# M119X.net
KiCad netlist of a schematic drawn in EAGLE
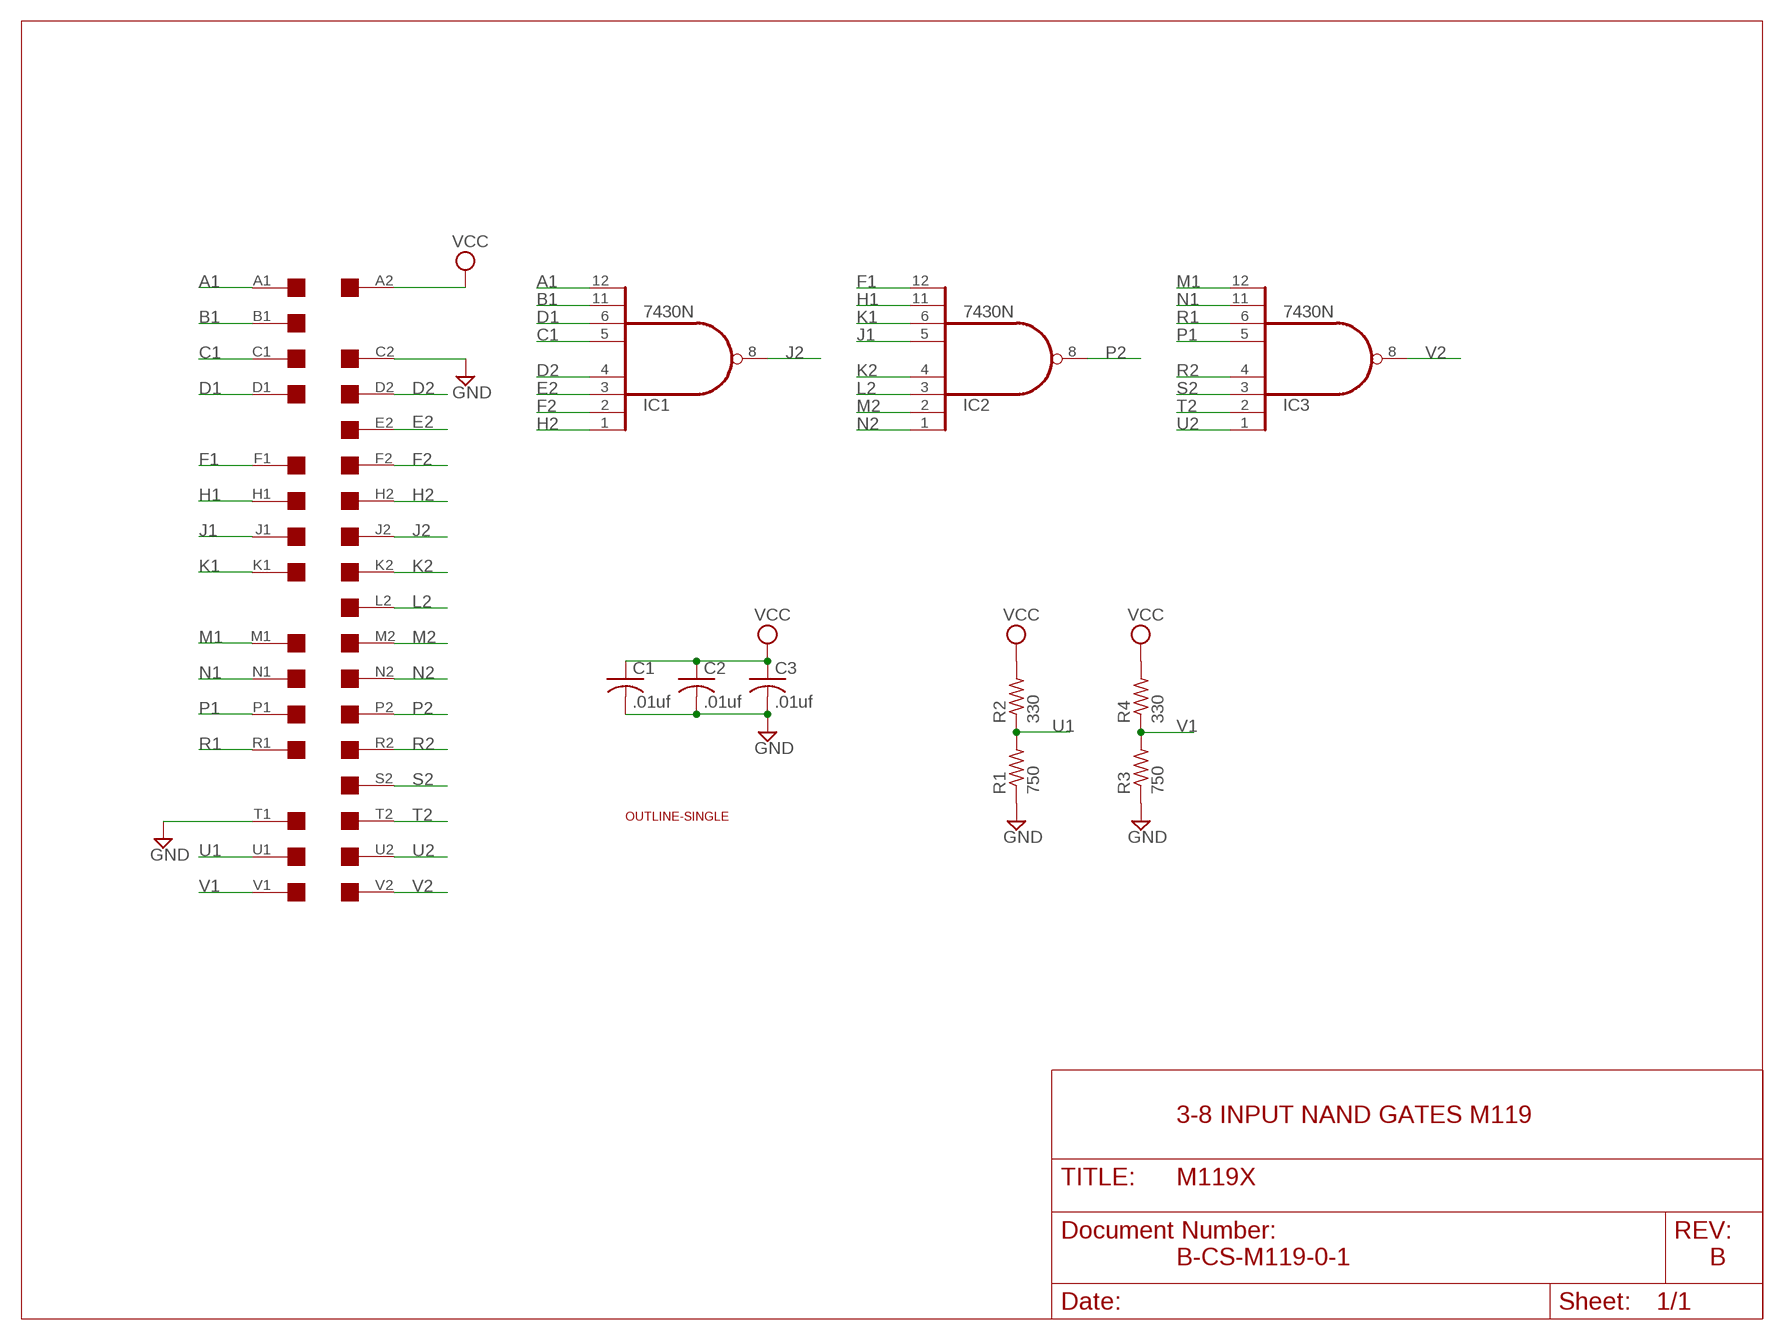
[diagram p0: schematic, sheet 1]

(export (version "E")
  (design (tool "Eeschema 10.0.6"))
  (components
    (comp (ref "C1")
      (value ".01uf")
      (footprint "eagle-import:C050-025X075")
      (libsource (lib "eagle-import") (part "C-US050-025X075"))
    )
    (comp (ref "C2")
      (value ".01uf")
      (footprint "eagle-import:C050-025X075")
      (libsource (lib "eagle-import") (part "C-US050-025X075"))
    )
    (comp (ref "C3")
      (value ".01uf")
      (footprint "eagle-import:C050-025X075")
      (libsource (lib "eagle-import") (part "C-US050-025X075"))
    )
    (comp (ref "IC1")
      (value "7430N")
      (footprint "eagle-import:DIL14")
      (libsource (lib "eagle-import") (part "7430N"))
    )
    (comp (ref "IC2")
      (value "7430N")
      (footprint "eagle-import:DIL14")
      (libsource (lib "eagle-import") (part "7430N"))
    )
    (comp (ref "IC3")
      (value "7430N")
      (footprint "eagle-import:DIL14")
      (libsource (lib "eagle-import") (part "7430N"))
    )
    (comp (ref "R1")
      (value "750")
      (footprint "eagle-import:0207_10")
      (libsource (lib "eagle-import") (part "R-US_0207/10"))
    )
    (comp (ref "R2")
      (value "330")
      (footprint "eagle-import:0207_10")
      (libsource (lib "eagle-import") (part "R-US_0207/10"))
    )
    (comp (ref "R3")
      (value "750")
      (footprint "eagle-import:0207_10")
      (libsource (lib "eagle-import") (part "R-US_0207/10"))
    )
    (comp (ref "R4")
      (value "330")
      (footprint "eagle-import:0207_10")
      (libsource (lib "eagle-import") (part "R-US_0207/10"))
    )
    (comp (ref "U$1")
      (value "OUTLINE-SINGLE")
      (footprint "eagle-import:SINGLE")
      (libsource (lib "eagle-import") (part "OUTLINE-SINGLE"))
    )
    (comp (ref "U$4")
      (value "SINGLE")
      (footprint "eagle-import:EDGE-CON2")
      (libsource (lib "eagle-import") (part "SINGLE"))
    )
  )
  (nets
    (net (code "1") (name "/A1") (class "Default")
      (node (ref "IC1") (pin "12") (pinfunction "I7_12") (pintype "input"))
      (node (ref "U$4") (pin "A1") (pinfunction "1_A1") (pintype "bidirectional"))
    )
    (net (code "2") (name "/B1") (class "Default")
      (node (ref "IC1") (pin "11") (pinfunction "I6_11") (pintype "input"))
      (node (ref "U$4") (pin "B1") (pinfunction "1_B1") (pintype "bidirectional"))
    )
    (net (code "3") (name "/C1") (class "Default")
      (node (ref "IC1") (pin "5") (pinfunction "I4_5") (pintype "input"))
      (node (ref "U$4") (pin "C1") (pinfunction "1_C1") (pintype "bidirectional"))
    )
    (net (code "4") (name "/D1") (class "Default")
      (node (ref "IC1") (pin "6") (pinfunction "I5_6") (pintype "input"))
      (node (ref "U$4") (pin "D1") (pinfunction "1_D1") (pintype "bidirectional"))
    )
    (net (code "5") (name "/D2") (class "Default")
      (node (ref "IC1") (pin "4") (pinfunction "I3_4") (pintype "input"))
      (node (ref "U$4") (pin "D2") (pinfunction "1_D2") (pintype "bidirectional"))
    )
    (net (code "6") (name "/E2") (class "Default")
      (node (ref "IC1") (pin "3") (pinfunction "I2_3") (pintype "input"))
      (node (ref "U$4") (pin "E2") (pinfunction "1_E2") (pintype "bidirectional"))
    )
    (net (code "7") (name "/F1") (class "Default")
      (node (ref "IC2") (pin "12") (pinfunction "I7_12") (pintype "input"))
      (node (ref "U$4") (pin "F1") (pinfunction "1_F1") (pintype "bidirectional"))
    )
    (net (code "8") (name "/F2") (class "Default")
      (node (ref "IC1") (pin "2") (pinfunction "I1_2") (pintype "input"))
      (node (ref "U$4") (pin "F2") (pinfunction "1_F2") (pintype "bidirectional"))
    )
    (net (code "9") (name "/H1") (class "Default")
      (node (ref "IC2") (pin "11") (pinfunction "I6_11") (pintype "input"))
      (node (ref "U$4") (pin "H1") (pinfunction "1_H1") (pintype "bidirectional"))
    )
    (net (code "10") (name "/H2") (class "Default")
      (node (ref "IC1") (pin "1") (pinfunction "I0_1") (pintype "input"))
      (node (ref "U$4") (pin "H2") (pinfunction "1_H2") (pintype "bidirectional"))
    )
    (net (code "11") (name "/J1") (class "Default")
      (node (ref "IC2") (pin "5") (pinfunction "I4_5") (pintype "input"))
      (node (ref "U$4") (pin "J1") (pinfunction "1_J1") (pintype "bidirectional"))
    )
    (net (code "12") (name "/J2") (class "Default")
      (node (ref "IC1") (pin "8") (pinfunction "O_8") (pintype "output"))
      (node (ref "U$4") (pin "J2") (pinfunction "1_J2") (pintype "bidirectional"))
    )
    (net (code "13") (name "/K1") (class "Default")
      (node (ref "IC2") (pin "6") (pinfunction "I5_6") (pintype "input"))
      (node (ref "U$4") (pin "K1") (pinfunction "1_K1") (pintype "bidirectional"))
    )
    (net (code "14") (name "/K2") (class "Default")
      (node (ref "IC2") (pin "4") (pinfunction "I3_4") (pintype "input"))
      (node (ref "U$4") (pin "K2") (pinfunction "1_K2") (pintype "bidirectional"))
    )
    (net (code "15") (name "/L2") (class "Default")
      (node (ref "IC2") (pin "3") (pinfunction "I2_3") (pintype "input"))
      (node (ref "U$4") (pin "L2") (pinfunction "1_L2") (pintype "bidirectional"))
    )
    (net (code "16") (name "/M1") (class "Default")
      (node (ref "IC3") (pin "12") (pinfunction "I7_12") (pintype "input"))
      (node (ref "U$4") (pin "M1") (pinfunction "1_M1") (pintype "bidirectional"))
    )
    (net (code "17") (name "/M2") (class "Default")
      (node (ref "IC2") (pin "2") (pinfunction "I1_2") (pintype "input"))
      (node (ref "U$4") (pin "M2") (pinfunction "1_M2") (pintype "bidirectional"))
    )
    (net (code "18") (name "/N1") (class "Default")
      (node (ref "IC3") (pin "11") (pinfunction "I6_11") (pintype "input"))
      (node (ref "U$4") (pin "N1") (pinfunction "1_N1") (pintype "bidirectional"))
    )
    (net (code "19") (name "/N2") (class "Default")
      (node (ref "IC2") (pin "1") (pinfunction "I0_1") (pintype "input"))
      (node (ref "U$4") (pin "N2") (pinfunction "1_N2") (pintype "bidirectional"))
    )
    (net (code "20") (name "/P1") (class "Default")
      (node (ref "IC3") (pin "5") (pinfunction "I4_5") (pintype "input"))
      (node (ref "U$4") (pin "P1") (pinfunction "1_P1") (pintype "bidirectional"))
    )
    (net (code "21") (name "/P2") (class "Default")
      (node (ref "IC2") (pin "8") (pinfunction "O_8") (pintype "output"))
      (node (ref "U$4") (pin "P2") (pinfunction "1_P2") (pintype "bidirectional"))
    )
    (net (code "22") (name "/R1") (class "Default")
      (node (ref "IC3") (pin "6") (pinfunction "I5_6") (pintype "input"))
      (node (ref "U$4") (pin "R1") (pinfunction "1_R1") (pintype "bidirectional"))
    )
    (net (code "23") (name "/R2") (class "Default")
      (node (ref "IC3") (pin "4") (pinfunction "I3_4") (pintype "input"))
      (node (ref "U$4") (pin "R2") (pinfunction "1_R2") (pintype "bidirectional"))
    )
    (net (code "24") (name "/S2") (class "Default")
      (node (ref "IC3") (pin "3") (pinfunction "I2_3") (pintype "input"))
      (node (ref "U$4") (pin "S2") (pinfunction "1_S2") (pintype "bidirectional"))
    )
    (net (code "25") (name "/T2") (class "Default")
      (node (ref "IC3") (pin "2") (pinfunction "I1_2") (pintype "input"))
      (node (ref "U$4") (pin "T2") (pinfunction "1_T2") (pintype "bidirectional"))
    )
    (net (code "26") (name "/U1") (class "Default")
      (node (ref "R1") (pin "2") (pinfunction "2_2") (pintype "passive"))
      (node (ref "R2") (pin "1") (pinfunction "1_1") (pintype "passive"))
      (node (ref "U$4") (pin "U1") (pinfunction "1_U1") (pintype "bidirectional"))
    )
    (net (code "27") (name "/U2") (class "Default")
      (node (ref "IC3") (pin "1") (pinfunction "I0_1") (pintype "input"))
      (node (ref "U$4") (pin "U2") (pinfunction "1_U2") (pintype "bidirectional"))
    )
    (net (code "28") (name "/V1") (class "Default")
      (node (ref "R3") (pin "2") (pinfunction "2_2") (pintype "passive"))
      (node (ref "R4") (pin "1") (pinfunction "1_1") (pintype "passive"))
      (node (ref "U$4") (pin "V1") (pinfunction "1_V1") (pintype "bidirectional"))
    )
    (net (code "29") (name "/V2") (class "Default")
      (node (ref "IC3") (pin "8") (pinfunction "O_8") (pintype "output"))
      (node (ref "U$4") (pin "V2") (pinfunction "1_V2") (pintype "bidirectional"))
    )
    (net (code "30") (name "GND") (class "Default")
      (node (ref "C1") (pin "2") (pinfunction "2_2") (pintype "passive"))
      (node (ref "C2") (pin "2") (pinfunction "2_2") (pintype "passive"))
      (node (ref "C3") (pin "2") (pinfunction "2_2") (pintype "passive"))
      (node (ref "R1") (pin "1") (pinfunction "1_1") (pintype "passive"))
      (node (ref "R3") (pin "1") (pinfunction "1_1") (pintype "passive"))
      (node (ref "U$4") (pin "C2") (pinfunction "1_C2") (pintype "bidirectional"))
      (node (ref "U$4") (pin "T1") (pinfunction "1_T1") (pintype "bidirectional"))
    )
    (net (code "31") (name "VCC") (class "Default")
      (node (ref "C1") (pin "1") (pinfunction "1_1") (pintype "passive"))
      (node (ref "C2") (pin "1") (pinfunction "1_1") (pintype "passive"))
      (node (ref "C3") (pin "1") (pinfunction "1_1") (pintype "passive"))
      (node (ref "R2") (pin "2") (pinfunction "2_2") (pintype "passive"))
      (node (ref "R4") (pin "2") (pinfunction "2_2") (pintype "passive"))
      (node (ref "U$4") (pin "A2") (pinfunction "1_A2") (pintype "bidirectional"))
    )
  )
)
